# openmv_motor_shield.net
KiCad netlist of a schematic drawn in EAGLE
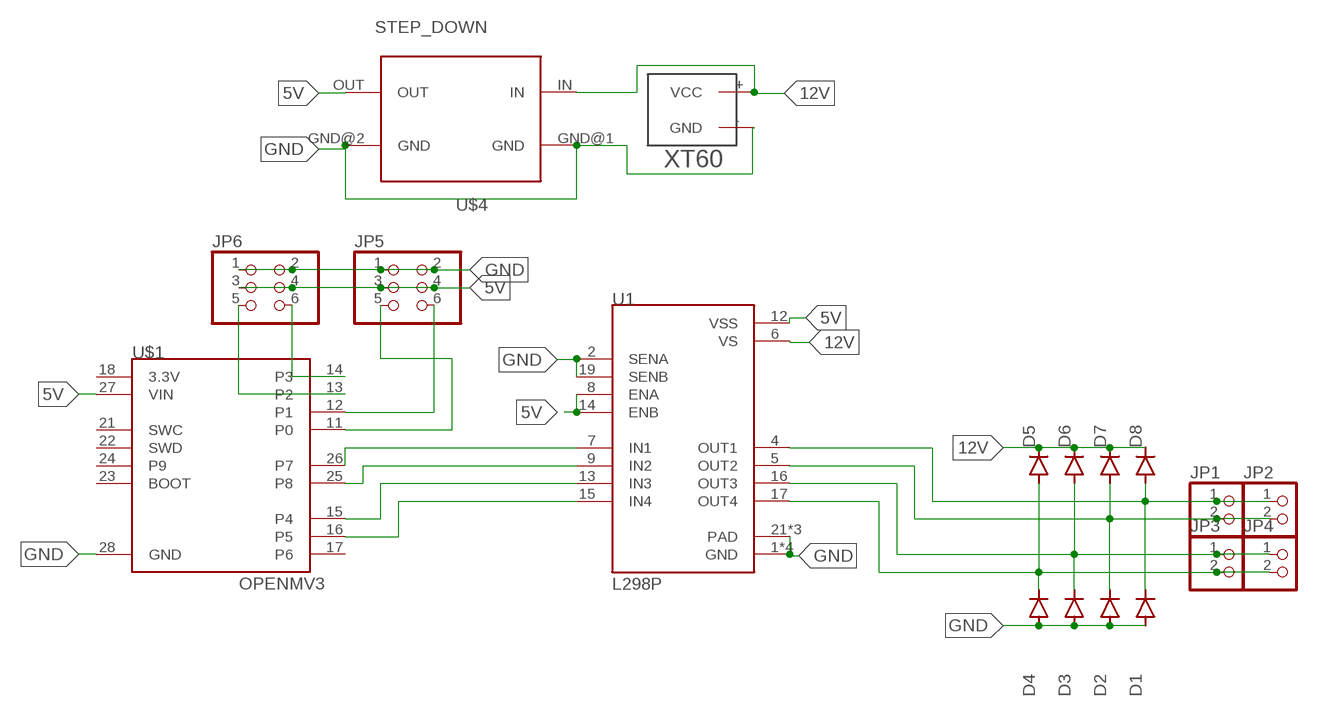
[diagram p0: schematic, sheet 1]

(export (version "E")
  (design (tool "Eeschema 10.0.6"))
  (components
    (comp (ref "D1")
      (value "SRP100")
      (footprint "eagle-import:DO41-10")
      (libsource (lib "eagle-import") (part "SRP100"))
    )
    (comp (ref "D2")
      (value "SRP100")
      (footprint "eagle-import:DO41-10")
      (libsource (lib "eagle-import") (part "SRP100"))
    )
    (comp (ref "D3")
      (value "SRP100")
      (footprint "eagle-import:DO41-10")
      (libsource (lib "eagle-import") (part "SRP100"))
    )
    (comp (ref "D4")
      (value "SRP100")
      (footprint "eagle-import:DO41-10")
      (libsource (lib "eagle-import") (part "SRP100"))
    )
    (comp (ref "D5")
      (value "SRP100")
      (footprint "eagle-import:DO41-10")
      (libsource (lib "eagle-import") (part "SRP100"))
    )
    (comp (ref "D6")
      (value "SRP100")
      (footprint "eagle-import:DO41-10")
      (libsource (lib "eagle-import") (part "SRP100"))
    )
    (comp (ref "D7")
      (value "SRP100")
      (footprint "eagle-import:DO41-10")
      (libsource (lib "eagle-import") (part "SRP100"))
    )
    (comp (ref "D8")
      (value "SRP100")
      (footprint "eagle-import:DO41-10")
      (libsource (lib "eagle-import") (part "SRP100"))
    )
    (comp (ref "JP1")
      (value "PINHD-1X2")
      (footprint "eagle-import:1X02")
      (libsource (lib "eagle-import") (part "PINHD-1X2"))
    )
    (comp (ref "JP2")
      (value "PINHD-1X2")
      (footprint "eagle-import:1X02")
      (libsource (lib "eagle-import") (part "PINHD-1X2"))
    )
    (comp (ref "JP3")
      (value "PINHD-1X2")
      (footprint "eagle-import:1X02")
      (libsource (lib "eagle-import") (part "PINHD-1X2"))
    )
    (comp (ref "JP4")
      (value "PINHD-1X2")
      (footprint "eagle-import:1X02")
      (libsource (lib "eagle-import") (part "PINHD-1X2"))
    )
    (comp (ref "JP5")
      (value "PINHD-2X3")
      (footprint "eagle-import:2X03")
      (libsource (lib "eagle-import") (part "PINHD-2X3"))
    )
    (comp (ref "JP6")
      (value "PINHD-2X3")
      (footprint "eagle-import:2X03")
      (libsource (lib "eagle-import") (part "PINHD-2X3"))
    )
    (comp (ref "U$1")
      (value "OPENMV3")
      (footprint "eagle-import:OPENMV3")
      (libsource (lib "eagle-import") (part "OPENMV3"))
    )
    (comp (ref "U$2")
      (value "XT60")
      (footprint "eagle-import:XT60")
      (libsource (lib "eagle-import") (part "XT60"))
    )
    (comp (ref "U$4")
      (value "STEP_DOWN")
      (footprint "eagle-import:STEP_DOWN_5V")
      (libsource (lib "eagle-import") (part "STEP_DOWN"))
    )
    (comp (ref "U1")
      (value "L298P")
      (footprint "eagle-import:SOIC127P1420X360-20N")
      (fields (field (name "MF") "STMicroelectronics"))
      (libsource (lib "eagle-import") (part "L298P"))
    )
  )
  (nets
    (net (code "1") (name "/3.3V") (class "Default")
      (node (ref "U$1") (pin "18") (pinfunction "3.3V_18") (pintype "power_in"))
    )
    (net (code "2") (name "5V") (class "Default")
      (node (ref "JP5") (pin "3") (pinfunction "3_3") (pintype "passive"))
      (node (ref "JP5") (pin "4") (pinfunction "4_4") (pintype "passive"))
      (node (ref "JP6") (pin "3") (pinfunction "3_3") (pintype "passive"))
      (node (ref "JP6") (pin "4") (pinfunction "4_4") (pintype "passive"))
      (node (ref "U$1") (pin "27") (pinfunction "VIN_27") (pintype "power_in"))
      (node (ref "U$4") (pin "OUT") (pinfunction "OUT_OUT") (pintype "bidirectional"))
      (node (ref "U1") (pin "12") (pinfunction "VSS_12") (pintype "power_in"))
      (node (ref "U1") (pin "14") (pinfunction "ENB_14") (pintype "input"))
      (node (ref "U1") (pin "8") (pinfunction "ENA_8") (pintype "input"))
    )
    (net (code "3") (name "12V") (class "Default")
      (node (ref "D5") (pin "C") (pinfunction "C_C") (pintype "passive"))
      (node (ref "D6") (pin "C") (pinfunction "C_C") (pintype "passive"))
      (node (ref "D7") (pin "C") (pinfunction "C_C") (pintype "passive"))
      (node (ref "D8") (pin "C") (pinfunction "C_C") (pintype "passive"))
      (node (ref "U$2") (pin "+") (pinfunction "VCC_+") (pintype "bidirectional"))
      (node (ref "U$4") (pin "IN") (pinfunction "IN_IN") (pintype "bidirectional"))
      (node (ref "U1") (pin "6") (pinfunction "VS_6") (pintype "power_in"))
    )
    (net (code "4") (name "GND") (class "Default")
      (node (ref "D1") (pin "A") (pinfunction "A_A") (pintype "passive"))
      (node (ref "D2") (pin "A") (pinfunction "A_A") (pintype "passive"))
      (node (ref "D3") (pin "A") (pinfunction "A_A") (pintype "passive"))
      (node (ref "D4") (pin "A") (pinfunction "A_A") (pintype "passive"))
      (node (ref "JP5") (pin "1") (pinfunction "1_1") (pintype "passive"))
      (node (ref "JP5") (pin "2") (pinfunction "2_2") (pintype "passive"))
      (node (ref "JP6") (pin "1") (pinfunction "1_1") (pintype "passive"))
      (node (ref "JP6") (pin "2") (pinfunction "2_2") (pintype "passive"))
      (node (ref "U$1") (pin "28") (pinfunction "GND_28") (pintype "power_in"))
      (node (ref "U$2") (pin "-") (pinfunction "GND_-") (pintype "bidirectional"))
      (node (ref "U$4") (pin "GND@1") (pinfunction "GND_GND@1") (pintype "bidirectional"))
      (node (ref "U$4") (pin "GND@2") (pinfunction "GND_GND@2") (pintype "bidirectional"))
      (node (ref "U1") (pin "1") (pinfunction "GND_1") (pintype "passive"))
      (node (ref "U1") (pin "10") (pinfunction "GND_10") (pintype "passive"))
      (node (ref "U1") (pin "11") (pinfunction "GND_11") (pintype "passive"))
      (node (ref "U1") (pin "19") (pinfunction "SENB_19") (pintype "input"))
      (node (ref "U1") (pin "2") (pinfunction "SENA_2") (pintype "input"))
      (node (ref "U1") (pin "20") (pinfunction "GND_20") (pintype "passive"))
      (node (ref "U1") (pin "21") (pinfunction "PAD_21") (pintype "passive"))
      (node (ref "U1") (pin "22") (pinfunction "PAD_22") (pintype "passive"))
      (node (ref "U1") (pin "23") (pinfunction "PAD_23") (pintype "passive"))
    )
    (net (code "5") (name "Net-(U$1-P0)") (class "Default")
      (node (ref "JP5") (pin "5") (pinfunction "5_5") (pintype "passive"))
      (node (ref "U$1") (pin "11") (pinfunction "P0_11") (pintype "bidirectional"))
    )
    (net (code "6") (name "Net-(U$1-P1)") (class "Default")
      (node (ref "JP5") (pin "6") (pinfunction "6_6") (pintype "passive"))
      (node (ref "U$1") (pin "12") (pinfunction "P1_12") (pintype "bidirectional"))
    )
    (net (code "7") (name "Net-(U$1-P2)") (class "Default")
      (node (ref "JP6") (pin "5") (pinfunction "5_5") (pintype "passive"))
      (node (ref "U$1") (pin "13") (pinfunction "P2_13") (pintype "bidirectional"))
    )
    (net (code "8") (name "Net-(U$1-P3)") (class "Default")
      (node (ref "JP6") (pin "6") (pinfunction "6_6") (pintype "passive"))
      (node (ref "U$1") (pin "14") (pinfunction "P3_14") (pintype "bidirectional"))
    )
    (net (code "9") (name "Net-(U$1-P4)") (class "Default")
      (node (ref "U$1") (pin "15") (pinfunction "P4_15") (pintype "bidirectional"))
      (node (ref "U1") (pin "13") (pinfunction "IN3_13") (pintype "input"))
    )
    (net (code "10") (name "Net-(U$1-P5)") (class "Default")
      (node (ref "U$1") (pin "16") (pinfunction "P5_16") (pintype "bidirectional"))
      (node (ref "U1") (pin "15") (pinfunction "IN4_15") (pintype "input"))
    )
    (net (code "11") (name "Net-(U$1-P7)") (class "Default")
      (node (ref "U$1") (pin "26") (pinfunction "P7_26") (pintype "bidirectional"))
      (node (ref "U1") (pin "7") (pinfunction "IN1_7") (pintype "input"))
    )
    (net (code "12") (name "Net-(U$1-P8)") (class "Default")
      (node (ref "U$1") (pin "25") (pinfunction "P8_25") (pintype "bidirectional"))
      (node (ref "U1") (pin "9") (pinfunction "IN2_9") (pintype "input"))
    )
    (net (code "13") (name "Net-(U1-OUT1)") (class "Default")
      (node (ref "D1") (pin "C") (pinfunction "C_C") (pintype "passive"))
      (node (ref "D8") (pin "A") (pinfunction "A_A") (pintype "passive"))
      (node (ref "JP1") (pin "1") (pinfunction "1_1") (pintype "passive"))
      (node (ref "JP2") (pin "1") (pinfunction "1_1") (pintype "passive"))
      (node (ref "U1") (pin "4") (pinfunction "OUT1_4") (pintype "output"))
    )
    (net (code "14") (name "Net-(U1-OUT2)") (class "Default")
      (node (ref "D2") (pin "C") (pinfunction "C_C") (pintype "passive"))
      (node (ref "D7") (pin "A") (pinfunction "A_A") (pintype "passive"))
      (node (ref "JP1") (pin "2") (pinfunction "2_2") (pintype "passive"))
      (node (ref "JP2") (pin "2") (pinfunction "2_2") (pintype "passive"))
      (node (ref "U1") (pin "5") (pinfunction "OUT2_5") (pintype "output"))
    )
    (net (code "15") (name "Net-(U1-OUT3)") (class "Default")
      (node (ref "D3") (pin "C") (pinfunction "C_C") (pintype "passive"))
      (node (ref "D6") (pin "A") (pinfunction "A_A") (pintype "passive"))
      (node (ref "JP3") (pin "1") (pinfunction "1_1") (pintype "passive"))
      (node (ref "JP4") (pin "1") (pinfunction "1_1") (pintype "passive"))
      (node (ref "U1") (pin "16") (pinfunction "OUT3_16") (pintype "output"))
    )
    (net (code "16") (name "Net-(U1-OUT4)") (class "Default")
      (node (ref "D4") (pin "C") (pinfunction "C_C") (pintype "passive"))
      (node (ref "D5") (pin "A") (pinfunction "A_A") (pintype "passive"))
      (node (ref "JP3") (pin "2") (pinfunction "2_2") (pintype "passive"))
      (node (ref "JP4") (pin "2") (pinfunction "2_2") (pintype "passive"))
      (node (ref "U1") (pin "17") (pinfunction "OUT4_17") (pintype "output"))
    )
    (net (code "17") (name "unconnected-(U$1-BOOT-Pad23)") (class "Default")
      (node (ref "U$1") (pin "23") (pinfunction "BOOT_23") (pintype "bidirectional"))
    )
    (net (code "18") (name "unconnected-(U$1-P6-Pad17)") (class "Default")
      (node (ref "U$1") (pin "17") (pinfunction "P6_17") (pintype "bidirectional"))
    )
    (net (code "19") (name "unconnected-(U$1-P9-Pad24)") (class "Default")
      (node (ref "U$1") (pin "24") (pinfunction "P9_24") (pintype "bidirectional"))
    )
    (net (code "20") (name "unconnected-(U$1-SWC-Pad21)") (class "Default")
      (node (ref "U$1") (pin "21") (pinfunction "SWC_21") (pintype "bidirectional"))
    )
    (net (code "21") (name "unconnected-(U$1-SWD-Pad22)") (class "Default")
      (node (ref "U$1") (pin "22") (pinfunction "SWD_22") (pintype "bidirectional"))
    )
  )
)
